# dc26-dev-board-apa102c-3.net
KiCad netlist of a schematic drawn in EAGLE
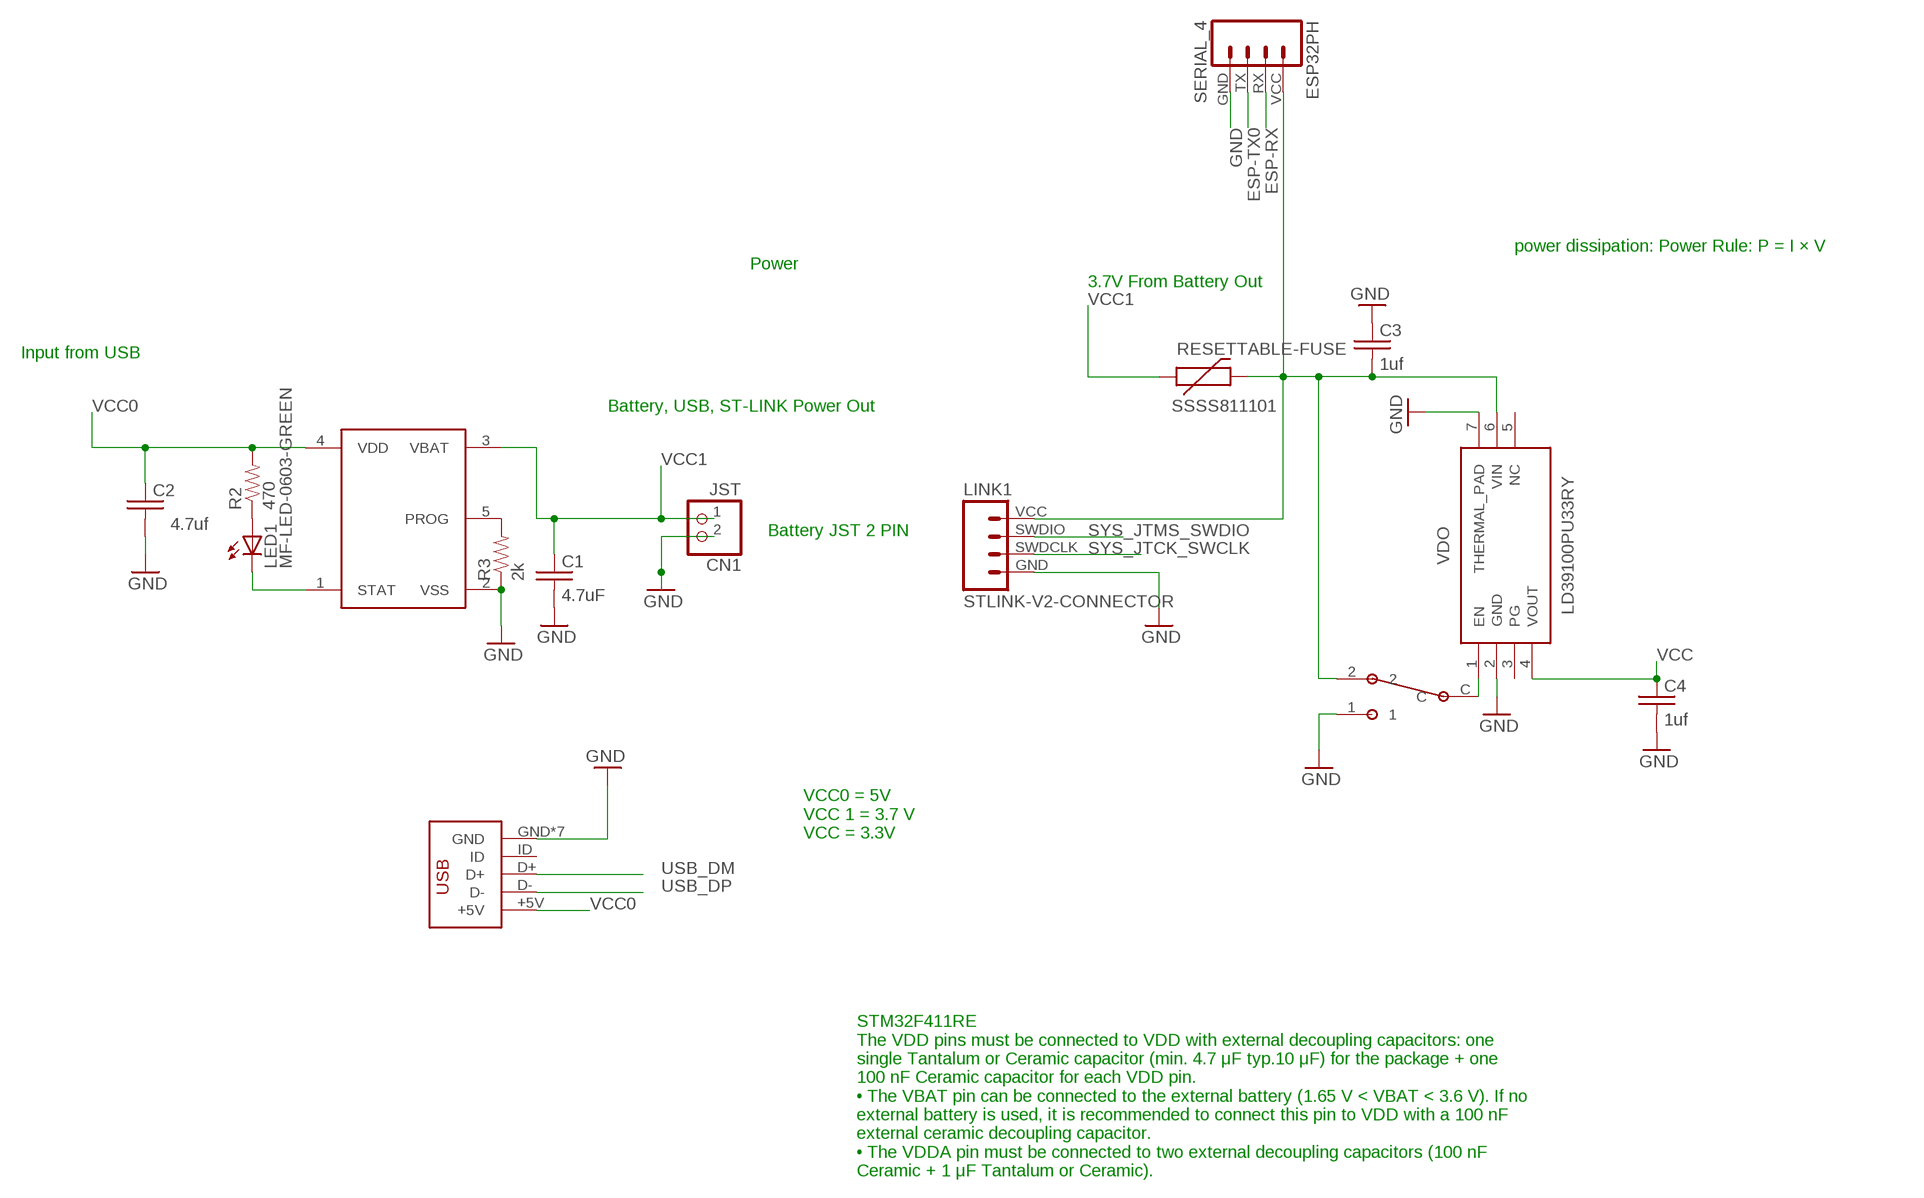
[diagram p0: schematic, sheet 1]
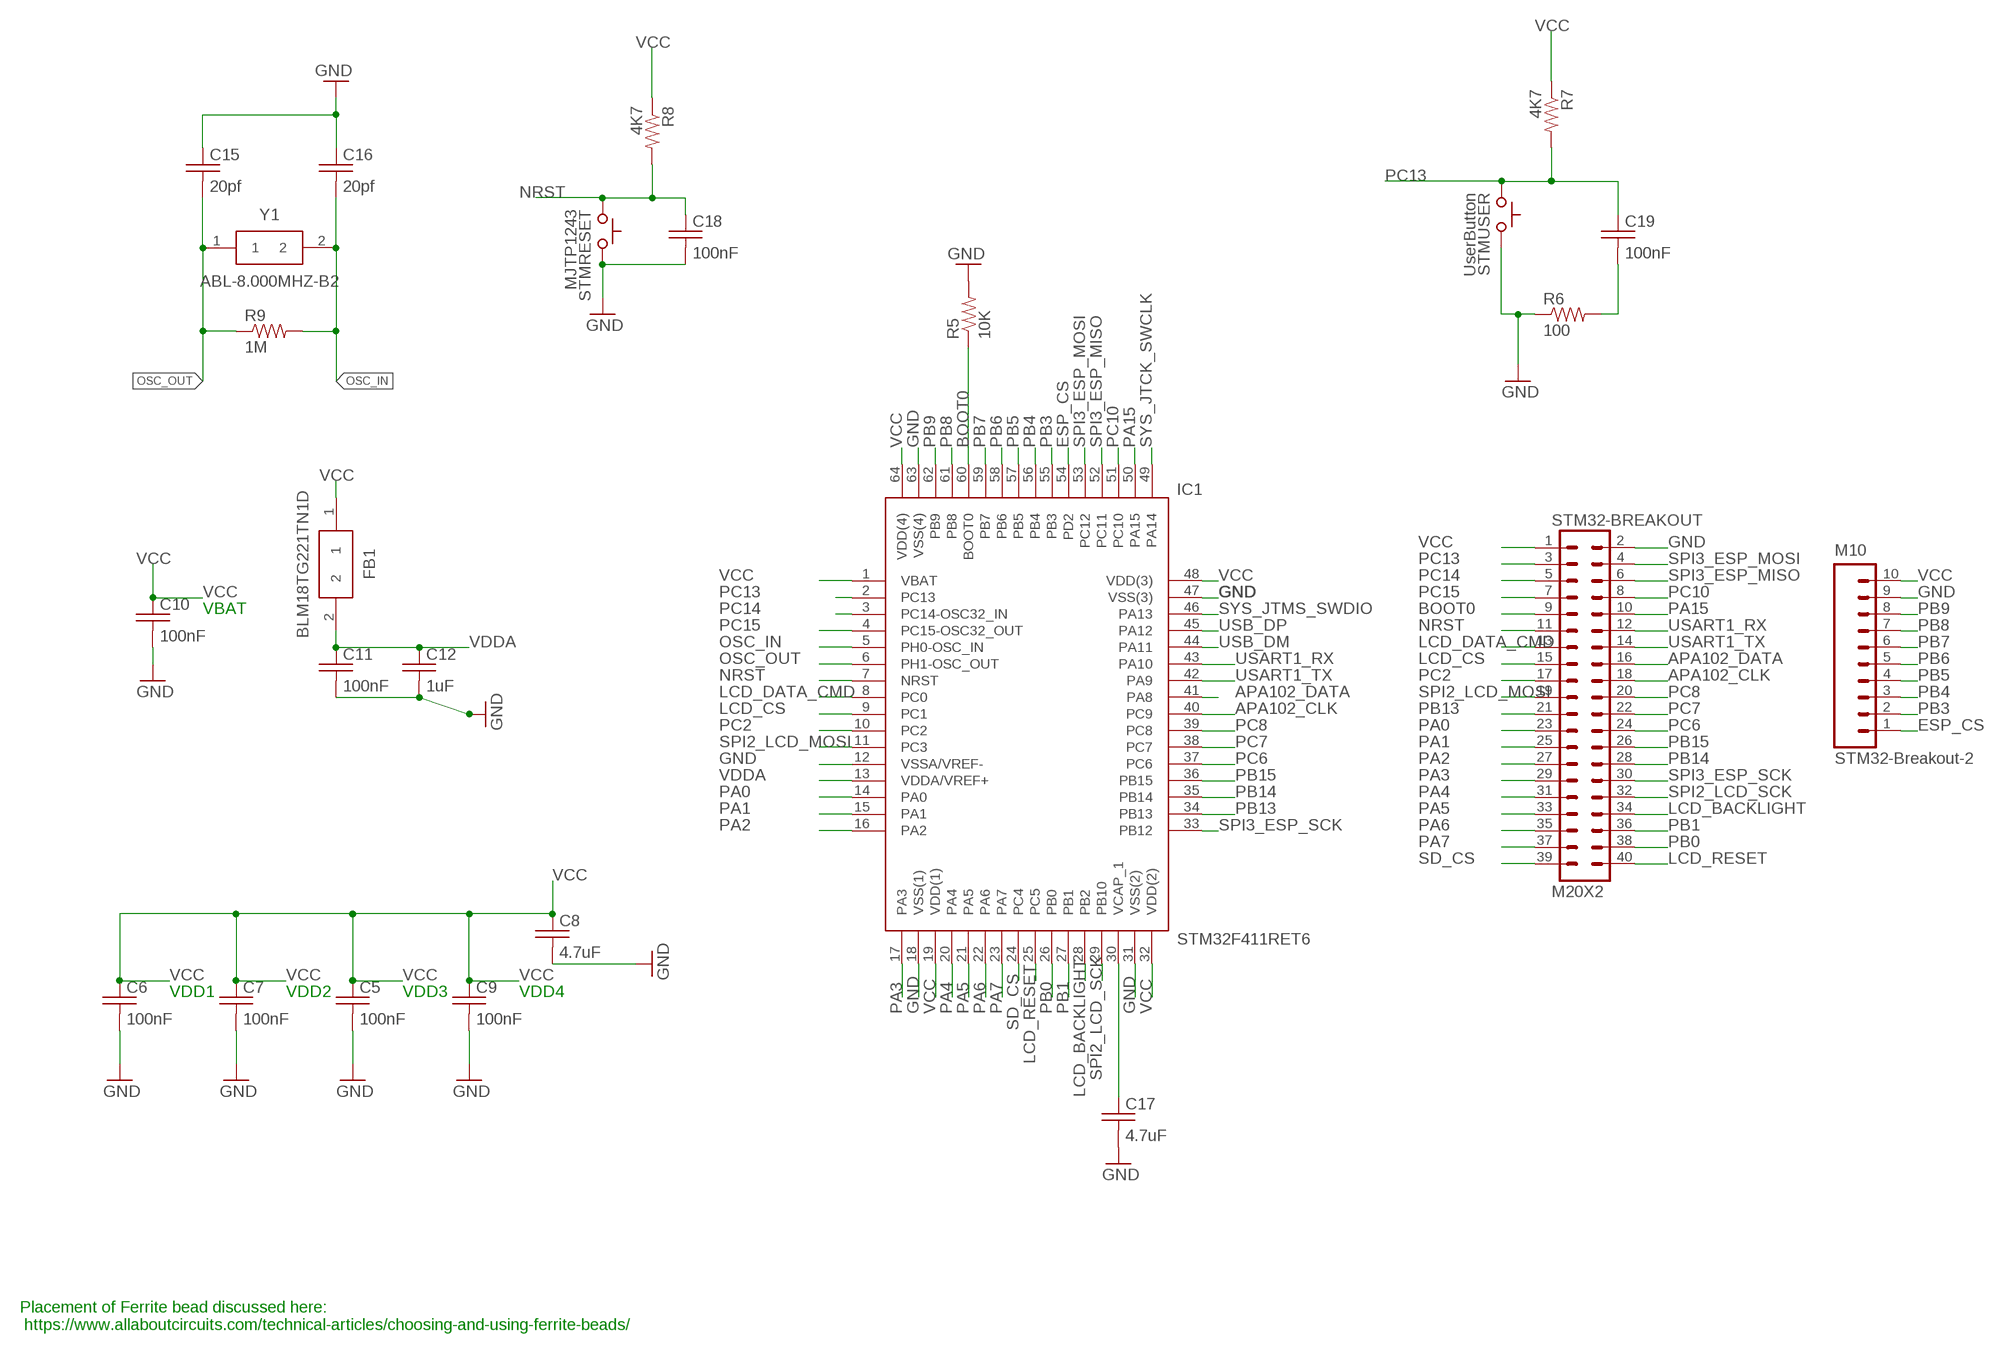
[diagram p1: schematic, sheet 2]
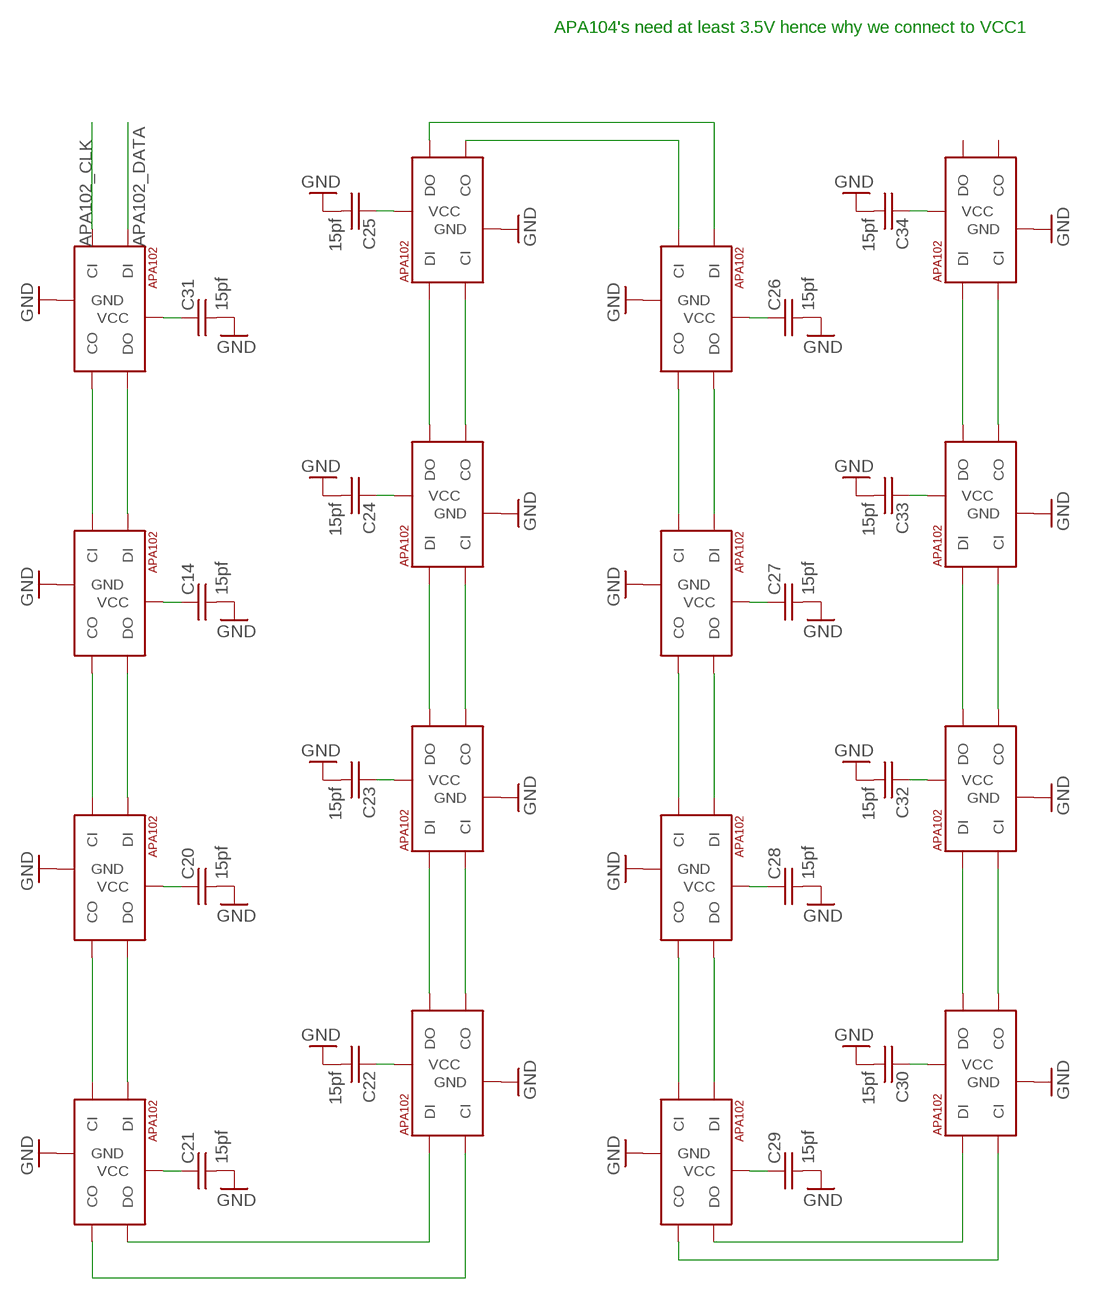
[diagram p2: schematic, sheet 3]
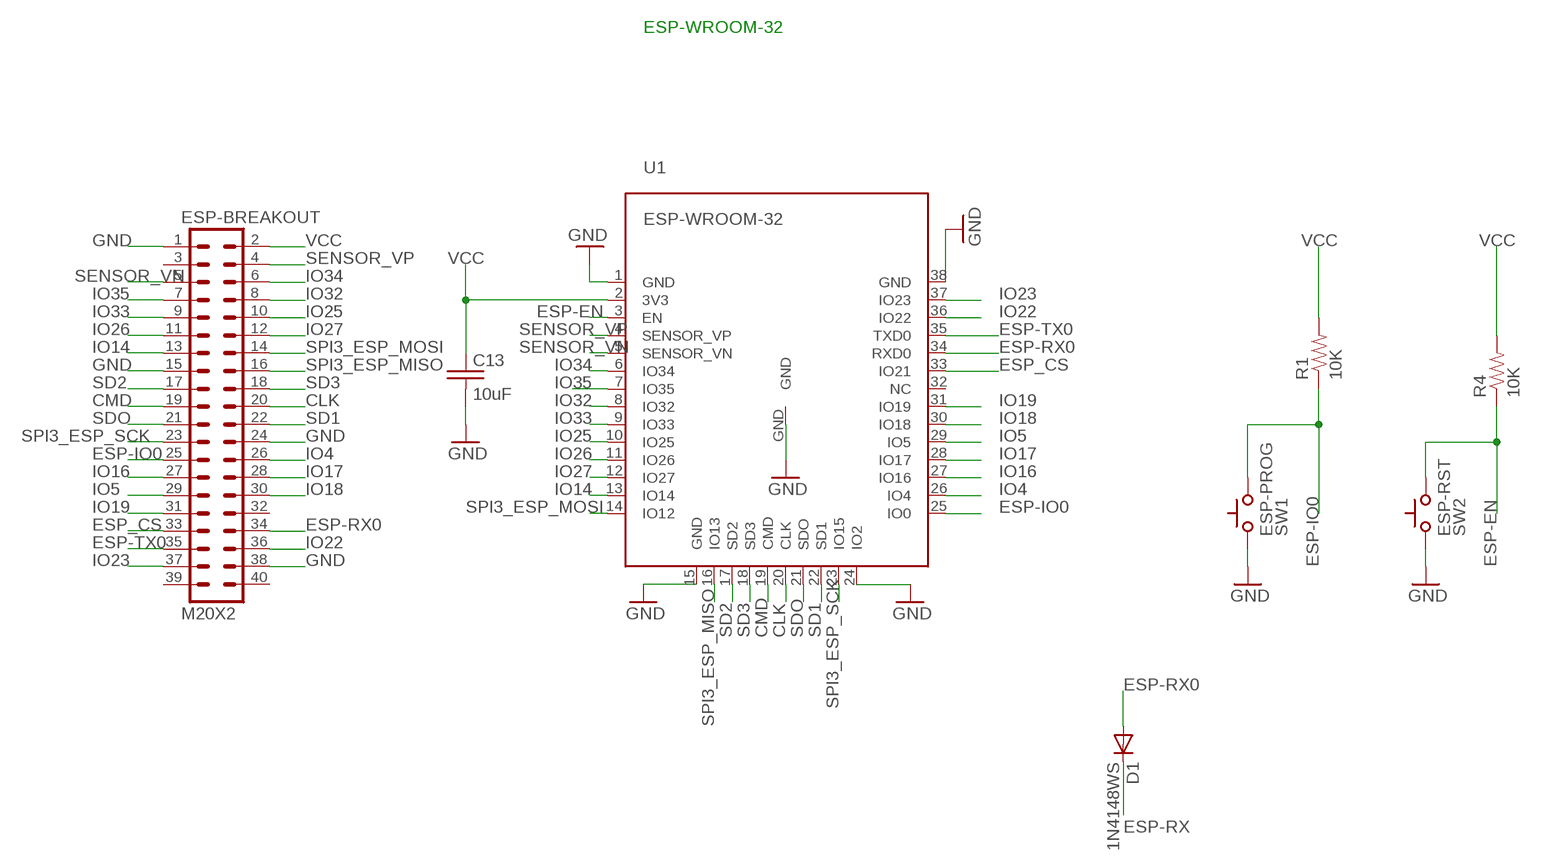
[diagram p3: schematic, sheet 4]
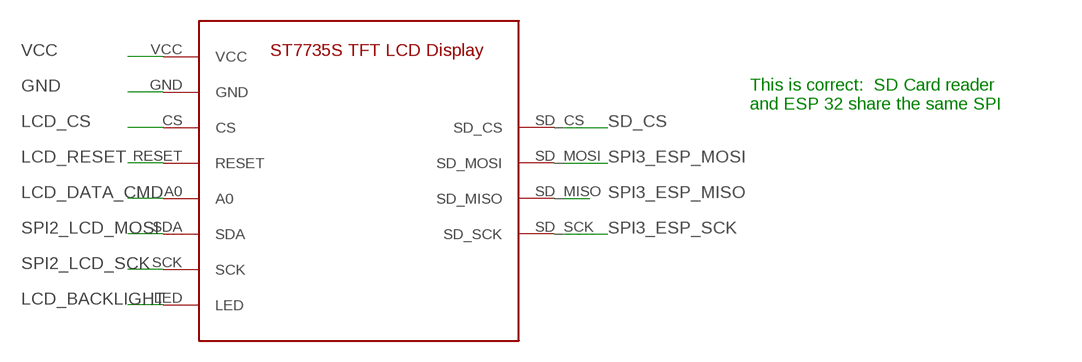
[diagram p4: schematic, sheet 5]
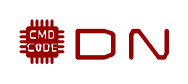
[diagram p5: schematic, sheet 6]
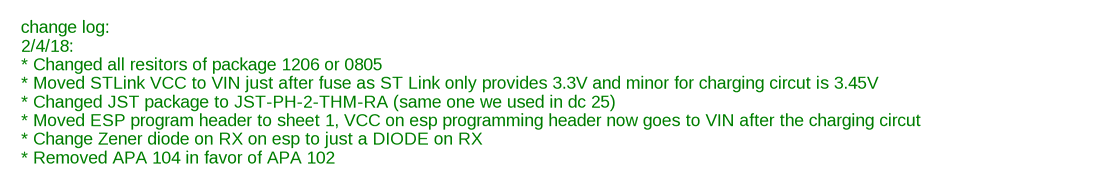
[diagram p6: schematic, sheet 7]

(export (version "E")
  (design (tool "Eeschema 10.0.6"))
  (components
    (comp (ref "C5")
      (value "100nF")
      (footprint "eagle-import:C0805")
      (libsource (lib "eagle-import") (part "C-USC0805"))
    )
    (comp (ref "C6")
      (value "100nF")
      (footprint "eagle-import:C0805")
      (libsource (lib "eagle-import") (part "C-USC0805"))
    )
    (comp (ref "C7")
      (value "100nF")
      (footprint "eagle-import:C0805")
      (libsource (lib "eagle-import") (part "C-USC0805"))
    )
    (comp (ref "C8")
      (value "4.7uF")
      (footprint "eagle-import:C0805")
      (libsource (lib "eagle-import") (part "C-USC0805"))
    )
    (comp (ref "C9")
      (value "100nF")
      (footprint "eagle-import:C0805")
      (libsource (lib "eagle-import") (part "C-USC0805"))
    )
    (comp (ref "C10")
      (value "100nF")
      (footprint "eagle-import:C0805")
      (libsource (lib "eagle-import") (part "C-USC0805"))
    )
    (comp (ref "C11")
      (value "100nF")
      (footprint "eagle-import:C0805")
      (libsource (lib "eagle-import") (part "C-USC0805"))
    )
    (comp (ref "C12")
      (value "1uF")
      (footprint "eagle-import:C0805")
      (libsource (lib "eagle-import") (part "C-USC0805"))
    )
    (comp (ref "C15")
      (value "20pf")
      (footprint "eagle-import:C0805")
      (libsource (lib "eagle-import") (part "C-USC0805"))
    )
    (comp (ref "C16")
      (value "20pf")
      (footprint "eagle-import:C0805")
      (libsource (lib "eagle-import") (part "C-USC0805"))
    )
    (comp (ref "C17")
      (value "4.7uF")
      (footprint "eagle-import:C0805")
      (libsource (lib "eagle-import") (part "C-USC0805"))
    )
    (comp (ref "C18")
      (value "100nF")
      (footprint "eagle-import:C0805")
      (libsource (lib "eagle-import") (part "C-USC0805"))
    )
    (comp (ref "C19")
      (value "100nF")
      (footprint "eagle-import:C0805")
      (libsource (lib "eagle-import") (part "C-USC0805"))
    )
    (comp (ref "FB1")
      (value "BLM18TG221TN1D")
      (footprint "eagle-import:BEADC1608X75N")
      (fields (field (name "RS_PART_NUMBER") "6197526"))
      (libsource (lib "eagle-import") (part "BLM18TG221TN1D"))
    )
    (comp (ref "IC1")
      (value "STM32F411RET6")
      (footprint "eagle-import:QFP50P1200X1200X160-64N")
      (fields (field (name "RS_PART_NUMBER") "1106617P"))
      (libsource (lib "eagle-import") (part "STM32F411RET6"))
    )
    (comp (ref "M10")
      (value "STM32-Breakout-2")
      (footprint "eagle-import:1X10")
      (libsource (lib "eagle-import") (part "M10SILK_FEMALE_PTH"))
    )
    (comp (ref "R5")
      (value "10K")
      (footprint "eagle-import:0805")
      (libsource (lib "eagle-import") (part "RESISTOR0805-RES"))
    )
    (comp (ref "R6")
      (value "100")
      (footprint "eagle-import:0805")
      (libsource (lib "eagle-import") (part "RESISTOR0805-RES"))
    )
    (comp (ref "R7")
      (value "4K7")
      (footprint "eagle-import:0805")
      (libsource (lib "eagle-import") (part "RESISTOR0805-RES"))
    )
    (comp (ref "R8")
      (value "4K7")
      (footprint "eagle-import:0805")
      (libsource (lib "eagle-import") (part "RESISTOR0805-RES"))
    )
    (comp (ref "R9")
      (value "1M")
      (footprint "eagle-import:0805")
      (libsource (lib "eagle-import") (part "RESISTOR0805-RES"))
    )
    (comp (ref "STM32-BREAKOUT")
      (value "M20X2")
      (footprint "eagle-import:2X20")
      (libsource (lib "eagle-import") (part "M20X2"))
    )
    (comp (ref "STMRESET")
      (value "MJTP1243")
      (footprint "eagle-import:TACTILE-2PIN-NARROW")
      (libsource (lib "eagle-import") (part "SWITCH_TACTILETACTILE-2PIN-NARROW"))
    )
    (comp (ref "STMUSER")
      (value "UserButton")
      (footprint "eagle-import:TACTILE-2PIN-NARROW")
      (libsource (lib "eagle-import") (part "SWITCH_TACTILETACTILE-2PIN-NARROW"))
    )
    (comp (ref "Y1")
      (value "ABL-8.000MHZ-B2")
      (footprint "eagle-import:HC_49US_(AT49)PTH")
      (libsource (lib "eagle-import") (part "ABL-8.000MHZ-B2"))
    )
    (comp (ref "C14")
      (value "15pf")
      (footprint "eagle-import:C0805")
      (libsource (lib "eagle-import") (part "C-USC0805"))
    )
    (comp (ref "C20")
      (value "15pf")
      (footprint "eagle-import:C0805")
      (libsource (lib "eagle-import") (part "C-USC0805"))
    )
    (comp (ref "C21")
      (value "15pf")
      (footprint "eagle-import:C0805")
      (libsource (lib "eagle-import") (part "C-USC0805"))
    )
    (comp (ref "C22")
      (value "15pf")
      (footprint "eagle-import:C0805")
      (libsource (lib "eagle-import") (part "C-USC0805"))
    )
    (comp (ref "C23")
      (value "15pf")
      (footprint "eagle-import:C0805")
      (libsource (lib "eagle-import") (part "C-USC0805"))
    )
    (comp (ref "C24")
      (value "15pf")
      (footprint "eagle-import:C0805")
      (libsource (lib "eagle-import") (part "C-USC0805"))
    )
    (comp (ref "C25")
      (value "15pf")
      (footprint "eagle-import:C0805")
      (libsource (lib "eagle-import") (part "C-USC0805"))
    )
    (comp (ref "C26")
      (value "15pf")
      (footprint "eagle-import:C0805")
      (libsource (lib "eagle-import") (part "C-USC0805"))
    )
    (comp (ref "C27")
      (value "15pf")
      (footprint "eagle-import:C0805")
      (libsource (lib "eagle-import") (part "C-USC0805"))
    )
    (comp (ref "C28")
      (value "15pf")
      (footprint "eagle-import:C0805")
      (libsource (lib "eagle-import") (part "C-USC0805"))
    )
    (comp (ref "C29")
      (value "15pf")
      (footprint "eagle-import:C0805")
      (libsource (lib "eagle-import") (part "C-USC0805"))
    )
    (comp (ref "C30")
      (value "15pf")
      (footprint "eagle-import:C0805")
      (libsource (lib "eagle-import") (part "C-USC0805"))
    )
    (comp (ref "C31")
      (value "15pf")
      (footprint "eagle-import:C0805")
      (libsource (lib "eagle-import") (part "C-USC0805"))
    )
    (comp (ref "C32")
      (value "15pf")
      (footprint "eagle-import:C0805")
      (libsource (lib "eagle-import") (part "C-USC0805"))
    )
    (comp (ref "C33")
      (value "15pf")
      (footprint "eagle-import:C0805")
      (libsource (lib "eagle-import") (part "C-USC0805"))
    )
    (comp (ref "C34")
      (value "15pf")
      (footprint "eagle-import:C0805")
      (libsource (lib "eagle-import") (part "C-USC0805"))
    )
    (comp (ref "U$5")
      (value "APA1025050")
      (footprint "eagle-import:APA102_5050")
      (libsource (lib "eagle-import") (part "APA1025050"))
    )
    (comp (ref "U$6")
      (value "APA1025050")
      (footprint "eagle-import:APA102_5050")
      (libsource (lib "eagle-import") (part "APA1025050"))
    )
    (comp (ref "U$7")
      (value "APA1025050")
      (footprint "eagle-import:APA102_5050")
      (libsource (lib "eagle-import") (part "APA1025050"))
    )
    (comp (ref "U$8")
      (value "APA1025050")
      (footprint "eagle-import:APA102_5050")
      (libsource (lib "eagle-import") (part "APA1025050"))
    )
    (comp (ref "U$9")
      (value "APA1025050")
      (footprint "eagle-import:APA102_5050")
      (libsource (lib "eagle-import") (part "APA1025050"))
    )
    (comp (ref "U$10")
      (value "APA1025050")
      (footprint "eagle-import:APA102_5050")
      (libsource (lib "eagle-import") (part "APA1025050"))
    )
    (comp (ref "U$11")
      (value "APA1025050")
      (footprint "eagle-import:APA102_5050")
      (libsource (lib "eagle-import") (part "APA1025050"))
    )
    (comp (ref "U$12")
      (value "APA1025050")
      (footprint "eagle-import:APA102_5050")
      (libsource (lib "eagle-import") (part "APA1025050"))
    )
    (comp (ref "U$13")
      (value "APA1025050")
      (footprint "eagle-import:APA102_5050")
      (libsource (lib "eagle-import") (part "APA1025050"))
    )
    (comp (ref "U$14")
      (value "APA1025050")
      (footprint "eagle-import:APA102_5050")
      (libsource (lib "eagle-import") (part "APA1025050"))
    )
    (comp (ref "U$15")
      (value "APA1025050")
      (footprint "eagle-import:APA102_5050")
      (libsource (lib "eagle-import") (part "APA1025050"))
    )
    (comp (ref "U$16")
      (value "APA1025050")
      (footprint "eagle-import:APA102_5050")
      (libsource (lib "eagle-import") (part "APA1025050"))
    )
    (comp (ref "U$17")
      (value "APA1025050")
      (footprint "eagle-import:APA102_5050")
      (libsource (lib "eagle-import") (part "APA1025050"))
    )
    (comp (ref "U$18")
      (value "APA1025050")
      (footprint "eagle-import:APA102_5050")
      (libsource (lib "eagle-import") (part "APA1025050"))
    )
    (comp (ref "U$19")
      (value "APA1025050")
      (footprint "eagle-import:APA102_5050")
      (libsource (lib "eagle-import") (part "APA1025050"))
    )
    (comp (ref "U$20")
      (value "APA1025050")
      (footprint "eagle-import:APA102_5050")
      (libsource (lib "eagle-import") (part "APA1025050"))
    )
    (comp (ref "U$1")
      (value "ST7735S_LCD_MODULE")
      (footprint "eagle-import:ST7735S_LCD_DISPLAY")
      (libsource (lib "eagle-import") (part "ST7735S_LCD_MODULE"))
    )
    (comp (ref "C13")
      (value "10uF")
      (footprint "eagle-import:C0805")
      (libsource (lib "eagle-import") (part "C-USC0805"))
    )
    (comp (ref "D1")
      (value "1N4148WS")
      (footprint "eagle-import:SOD-323")
      (libsource (lib "eagle-import") (part "DIODESOD"))
    )
    (comp (ref "ESP-BREAKOUT")
      (value "M20X2")
      (footprint "eagle-import:2X20")
      (libsource (lib "eagle-import") (part "M20X2"))
    )
    (comp (ref "ESP-PROG")
      (value "SW1")
      (footprint "eagle-import:TACTILE-2PIN-NARROW")
      (libsource (lib "eagle-import") (part "SWITCH_TACTILETACTILE-2PIN-NARROW"))
    )
    (comp (ref "ESP-RST")
      (value "SW2")
      (footprint "eagle-import:TACTILE-2PIN-NARROW")
      (libsource (lib "eagle-import") (part "SWITCH_TACTILETACTILE-2PIN-NARROW"))
    )
    (comp (ref "R1")
      (value "10K")
      (footprint "eagle-import:0805")
      (libsource (lib "eagle-import") (part "RESISTOR0805-RES"))
    )
    (comp (ref "R4")
      (value "10K")
      (footprint "eagle-import:0805")
      (libsource (lib "eagle-import") (part "RESISTOR0805-RES"))
    )
    (comp (ref "U1")
      (value "ESP-WROOM-32")
      (footprint "eagle-import:ESP-WROOM-32")
      (libsource (lib "eagle-import") (part "ESP-WROOM-32"))
    )
    (comp (ref "U$2")
      (value "CMD_C0DE_LOGO")
      (footprint "eagle-import:CMD_C0DE_LOGO")
      (libsource (lib "eagle-import") (part "CMD_C0DE_LOGO"))
    )
    (comp (ref "U$3")
      (value "DARKNET_DD")
      (footprint "eagle-import:DARKNET_D")
      (libsource (lib "eagle-import") (part "DARKNET_DD"))
    )
    (comp (ref "U$4")
      (value "DARKNET_NN")
      (footprint "eagle-import:DARKNET_N")
      (libsource (lib "eagle-import") (part "DARKNET_NN"))
    )
    (comp (ref "C1")
      (value "4.7uF")
      (footprint "eagle-import:C0805")
      (libsource (lib "eagle-import") (part "C-USC0805"))
    )
    (comp (ref "C2")
      (value "4.7uf")
      (footprint "eagle-import:C0805")
      (libsource (lib "eagle-import") (part "C-USC0805"))
    )
    (comp (ref "C3")
      (value "1uf")
      (footprint "eagle-import:C0805")
      (libsource (lib "eagle-import") (part "C-USC0805"))
    )
    (comp (ref "C4")
      (value "1uf")
      (footprint "eagle-import:C0805")
      (libsource (lib "eagle-import") (part "C-USC0805"))
    )
    (comp (ref "CHARGING_CIRCUT")
      (value "MCP73831")
      (footprint "eagle-import:SOT23-5")
      (libsource (lib "eagle-import") (part "DS21984E"))
    )
    (comp (ref "CN1")
      (value "JST")
      (footprint "eagle-import:JST-PH-2-THM-RA")
      (libsource (lib "eagle-import") (part "JST_2PIN-THM-RA"))
    )
    (comp (ref "ESP32PH")
      (value "SERIAL_4")
      (footprint "eagle-import:SERIAL_HEADER_4")
      (libsource (lib "eagle-import") (part "SERIAL_4"))
    )
    (comp (ref "LED1")
      (value "MF-LED-0603-GREEN")
      (footprint "eagle-import:LED-1206")
      (libsource (lib "eagle-import") (part "LED1206"))
    )
    (comp (ref "LINK1")
      (value "STLINK-V2-CONNECTOR")
      (footprint "eagle-import:1X04")
      (libsource (lib "eagle-import") (part "STLINK-V2-CONNECTOR"))
    )
    (comp (ref "P1")
      (value "SSSS811101")
      (footprint "eagle-import:SPDT_SSAJ120100")
      (libsource (lib "eagle-import") (part "SWITCH_SPDT"))
    )
    (comp (ref "R2")
      (value "470")
      (footprint "eagle-import:0805")
      (libsource (lib "eagle-import") (part "RESISTOR0805-RES"))
    )
    (comp (ref "R3")
      (value "2k")
      (footprint "eagle-import:0805")
      (libsource (lib "eagle-import") (part "RESISTOR0805-RES"))
    )
    (comp (ref "RESETTABLE-FUSE")
      (value "SSSS811101")
      (footprint "eagle-import:PTC-1206")
      (libsource (lib "eagle-import") (part "PTCSMD"))
    )
    (comp (ref "USB")
      (value "DX4R005JJ2DX4R005JJ2")
      (footprint "eagle-import:DX4R005JJ2")
      (libsource (lib "eagle-import") (part "DX4R005JJ2DX4R005JJ2"))
    )
    (comp (ref "VDO")
      (value "LD39100PU33RY")
      (footprint "eagle-import:SON95P300X300X90-7N")
      (libsource (lib "eagle-import") (part "LD39100PU33RY"))
    )
  )
  (nets
    (net (code "1") (name "APA102_CLK") (class "Default")
      (node (ref "IC1") (pin "40") (pinfunction "PC9_40") (pintype "passive"))
      (node (ref "STM32-BREAKOUT") (pin "18") (pinfunction "18_18") (pintype "passive"))
      (node (ref "U$8") (pin "5") (pinfunction "CI_5") (pintype "bidirectional"))
    )
    (net (code "2") (name "APA102_DATA") (class "Default")
      (node (ref "IC1") (pin "41") (pinfunction "PA8_41") (pintype "passive"))
      (node (ref "STM32-BREAKOUT") (pin "16") (pinfunction "16_16") (pintype "passive"))
      (node (ref "U$8") (pin "4") (pinfunction "DI_4") (pintype "bidirectional"))
    )
    (net (code "3") (name "BOOT0") (class "Default")
      (node (ref "IC1") (pin "60") (pinfunction "BOOT0_60") (pintype "passive"))
      (node (ref "R5") (pin "1") (pinfunction "1_1") (pintype "passive"))
      (node (ref "STM32-BREAKOUT") (pin "9") (pinfunction "9_9") (pintype "passive"))
    )
    (net (code "4") (name "CLK") (class "Default")
      (node (ref "ESP-BREAKOUT") (pin "20") (pinfunction "20_20") (pintype "passive"))
      (node (ref "U1") (pin "20") (pinfunction "CLK_20") (pintype "bidirectional"))
    )
    (net (code "5") (name "CMD") (class "Default")
      (node (ref "ESP-BREAKOUT") (pin "19") (pinfunction "19_19") (pintype "passive"))
      (node (ref "U1") (pin "19") (pinfunction "CMD_19") (pintype "bidirectional"))
    )
    (net (code "6") (name "ESP-EN") (class "Default")
      (node (ref "ESP-RST") (pin "P$1") (pinfunction "A_P$1") (pintype "passive"))
      (node (ref "R4") (pin "1") (pinfunction "1_1") (pintype "passive"))
      (node (ref "U1") (pin "3") (pinfunction "EN_3") (pintype "bidirectional"))
    )
    (net (code "7") (name "ESP-IO0") (class "Default")
      (node (ref "ESP-BREAKOUT") (pin "25") (pinfunction "25_25") (pintype "passive"))
      (node (ref "ESP-PROG") (pin "P$1") (pinfunction "A_P$1") (pintype "passive"))
      (node (ref "R1") (pin "1") (pinfunction "1_1") (pintype "passive"))
      (node (ref "U1") (pin "25") (pinfunction "IO0_25") (pintype "bidirectional"))
    )
    (net (code "8") (name "ESP-RX") (class "Default")
      (node (ref "D1") (pin "1") (pinfunction "C_1") (pintype "passive"))
      (node (ref "ESP32PH") (pin "RX") (pinfunction "RX_RX") (pintype "bidirectional"))
    )
    (net (code "9") (name "ESP-RX0") (class "Default")
      (node (ref "D1") (pin "2") (pinfunction "A_2") (pintype "passive"))
      (node (ref "ESP-BREAKOUT") (pin "34") (pinfunction "34_34") (pintype "passive"))
      (node (ref "U1") (pin "34") (pinfunction "RXD0_34") (pintype "bidirectional"))
    )
    (net (code "10") (name "ESP-TX0") (class "Default")
      (node (ref "ESP-BREAKOUT") (pin "35") (pinfunction "35_35") (pintype "passive"))
      (node (ref "ESP32PH") (pin "TX") (pinfunction "TX_TX") (pintype "input"))
      (node (ref "U1") (pin "35") (pinfunction "TXD0_35") (pintype "bidirectional"))
    )
    (net (code "11") (name "ESP_CS") (class "Default")
      (node (ref "ESP-BREAKOUT") (pin "33") (pinfunction "33_33") (pintype "passive"))
      (node (ref "IC1") (pin "54") (pinfunction "PD2_54") (pintype "passive"))
      (node (ref "M10") (pin "1") (pinfunction "1_1") (pintype "passive"))
      (node (ref "U1") (pin "33") (pinfunction "IO21_33") (pintype "bidirectional"))
    )
    (net (code "12") (name "GND") (class "Default")
      (node (ref "C1") (pin "2") (pinfunction "2_2") (pintype "passive"))
      (node (ref "C10") (pin "2") (pinfunction "2_2") (pintype "passive"))
      (node (ref "C11") (pin "2") (pinfunction "2_2") (pintype "passive"))
      (node (ref "C12") (pin "2") (pinfunction "2_2") (pintype "passive"))
      (node (ref "C13") (pin "2") (pinfunction "2_2") (pintype "passive"))
      (node (ref "C14") (pin "2") (pinfunction "2_2") (pintype "passive"))
      (node (ref "C15") (pin "1") (pinfunction "1_1") (pintype "passive"))
      (node (ref "C16") (pin "1") (pinfunction "1_1") (pintype "passive"))
      (node (ref "C17") (pin "2") (pinfunction "2_2") (pintype "passive"))
      (node (ref "C18") (pin "2") (pinfunction "2_2") (pintype "passive"))
      (node (ref "C2") (pin "2") (pinfunction "2_2") (pintype "passive"))
      (node (ref "C20") (pin "2") (pinfunction "2_2") (pintype "passive"))
      (node (ref "C21") (pin "2") (pinfunction "2_2") (pintype "passive"))
      (node (ref "C22") (pin "2") (pinfunction "2_2") (pintype "passive"))
      (node (ref "C23") (pin "2") (pinfunction "2_2") (pintype "passive"))
      (node (ref "C24") (pin "2") (pinfunction "2_2") (pintype "passive"))
      (node (ref "C25") (pin "2") (pinfunction "2_2") (pintype "passive"))
      (node (ref "C26") (pin "2") (pinfunction "2_2") (pintype "passive"))
      (node (ref "C27") (pin "2") (pinfunction "2_2") (pintype "passive"))
      (node (ref "C28") (pin "2") (pinfunction "2_2") (pintype "passive"))
      (node (ref "C29") (pin "2") (pinfunction "2_2") (pintype "passive"))
      (node (ref "C3") (pin "1") (pinfunction "1_1") (pintype "passive"))
      (node (ref "C30") (pin "2") (pinfunction "2_2") (pintype "passive"))
      (node (ref "C31") (pin "2") (pinfunction "2_2") (pintype "passive"))
      (node (ref "C32") (pin "2") (pinfunction "2_2") (pintype "passive"))
      (node (ref "C33") (pin "2") (pinfunction "2_2") (pintype "passive"))
      (node (ref "C34") (pin "2") (pinfunction "2_2") (pintype "passive"))
      (node (ref "C4") (pin "2") (pinfunction "2_2") (pintype "passive"))
      (node (ref "C5") (pin "2") (pinfunction "2_2") (pintype "passive"))
      (node (ref "C6") (pin "2") (pinfunction "2_2") (pintype "passive"))
      (node (ref "C7") (pin "2") (pinfunction "2_2") (pintype "passive"))
      (node (ref "C8") (pin "2") (pinfunction "2_2") (pintype "passive"))
      (node (ref "C9") (pin "2") (pinfunction "2_2") (pintype "passive"))
      (node (ref "CHARGING_CIRCUT") (pin "2") (pinfunction "VSS_2") (pintype "bidirectional"))
      (node (ref "CN1") (pin "2") (pinfunction "1_2") (pintype "passive"))
      (node (ref "ESP-BREAKOUT") (pin "1") (pinfunction "1_1") (pintype "passive"))
      (node (ref "ESP-BREAKOUT") (pin "15") (pinfunction "15_15") (pintype "passive"))
      (node (ref "ESP-BREAKOUT") (pin "24") (pinfunction "24_24") (pintype "passive"))
      (node (ref "ESP-BREAKOUT") (pin "38") (pinfunction "38_38") (pintype "passive"))
      (node (ref "ESP-PROG") (pin "P$2") (pinfunction "C_P$2") (pintype "passive"))
      (node (ref "ESP-RST") (pin "P$2") (pinfunction "C_P$2") (pintype "passive"))
      (node (ref "ESP32PH") (pin "GND") (pinfunction "GND_GND") (pintype "power_in"))
      (node (ref "IC1") (pin "12") (pinfunction "VSSA/VREF-_12") (pintype "passive"))
      (node (ref "IC1") (pin "18") (pinfunction "VSS(1)_18") (pintype "passive"))
      (node (ref "IC1") (pin "31") (pinfunction "VSS(2)_31") (pintype "passive"))
      (node (ref "IC1") (pin "47") (pinfunction "VSS(3)_47") (pintype "passive"))
      (node (ref "IC1") (pin "63") (pinfunction "VSS(4)_63") (pintype "passive"))
      (node (ref "LINK1") (pin "GND") (pinfunction "GND_GND") (pintype "power_in"))
      (node (ref "M10") (pin "9") (pinfunction "9_9") (pintype "passive"))
      (node (ref "P1") (pin "1") (pinfunction "1_1") (pintype "bidirectional"))
      (node (ref "R3") (pin "1") (pinfunction "1_1") (pintype "passive"))
      (node (ref "R5") (pin "2") (pinfunction "2_2") (pintype "passive"))
      (node (ref "R6") (pin "1") (pinfunction "1_1") (pintype "passive"))
      (node (ref "STM32-BREAKOUT") (pin "2") (pinfunction "2_2") (pintype "passive"))
      (node (ref "STMRESET") (pin "P$1") (pinfunction "A_P$1") (pintype "passive"))
      (node (ref "STMUSER") (pin "P$1") (pinfunction "A_P$1") (pintype "passive"))
      (node (ref "U$1") (pin "GND") (pinfunction "GND_GND") (pintype "bidirectional"))
      (node (ref "U$10") (pin "6") (pinfunction "GND_6") (pintype "bidirectional"))
      (node (ref "U$11") (pin "6") (pinfunction "GND_6") (pintype "bidirectional"))
      (node (ref "U$12") (pin "6") (pinfunction "GND_6") (pintype "bidirectional"))
      (node (ref "U$13") (pin "6") (pinfunction "GND_6") (pintype "bidirectional"))
      (node (ref "U$14") (pin "6") (pinfunction "GND_6") (pintype "bidirectional"))
      (node (ref "U$15") (pin "6") (pinfunction "GND_6") (pintype "bidirectional"))
      (node (ref "U$16") (pin "6") (pinfunction "GND_6") (pintype "bidirectional"))
      (node (ref "U$17") (pin "6") (pinfunction "GND_6") (pintype "bidirectional"))
      (node (ref "U$18") (pin "6") (pinfunction "GND_6") (pintype "bidirectional"))
      (node (ref "U$19") (pin "6") (pinfunction "GND_6") (pintype "bidirectional"))
      (node (ref "U$20") (pin "6") (pinfunction "GND_6") (pintype "bidirectional"))
      (node (ref "U$5") (pin "6") (pinfunction "GND_6") (pintype "bidirectional"))
      (node (ref "U$6") (pin "6") (pinfunction "GND_6") (pintype "bidirectional"))
      (node (ref "U$7") (pin "6") (pinfunction "GND_6") (pintype "bidirectional"))
      (node (ref "U$8") (pin "6") (pinfunction "GND_6") (pintype "bidirectional"))
      (node (ref "U$9") (pin "6") (pinfunction "GND_6") (pintype "bidirectional"))
      (node (ref "U1") (pin "1") (pinfunction "GND_1") (pintype "bidirectional"))
      (node (ref "U1") (pin "15") (pinfunction "GND_15") (pintype "bidirectional"))
      (node (ref "U1") (pin "24") (pinfunction "IO2_24") (pintype "bidirectional"))
      (node (ref "U1") (pin "38") (pinfunction "GND_38") (pintype "bidirectional"))
      (node (ref "U1") (pin "GND") (pinfunction "GND_GND") (pintype "bidirectional"))
      (node (ref "USB") (pin "GND") (pinfunction "GND_GND") (pintype "bidirectional"))
      (node (ref "USB") (pin "P$10") (pinfunction "GND_P$10") (pintype "bidirectional"))
      (node (ref "USB") (pin "P$11") (pinfunction "GND_P$11") (pintype "bidirectional"))
      (node (ref "USB") (pin "P$6") (pinfunction "GND_P$6") (pintype "bidirectional"))
      (node (ref "USB") (pin "P$7") (pinfunction "GND_P$7") (pintype "bidirectional"))
      (node (ref "USB") (pin "P$8") (pinfunction "GND_P$8") (pintype "bidirectional"))
      (node (ref "USB") (pin "P$9") (pinfunction "GND_P$9") (pintype "bidirectional"))
      (node (ref "VDO") (pin "2") (pinfunction "GND_2") (pintype "passive"))
      (node (ref "VDO") (pin "7") (pinfunction "THERMAL_PAD_7") (pintype "passive"))
    )
    (net (code "13") (name "IO4") (class "Default")
      (node (ref "ESP-BREAKOUT") (pin "26") (pinfunction "26_26") (pintype "passive"))
      (node (ref "U1") (pin "26") (pinfunction "IO4_26") (pintype "bidirectional"))
    )
    (net (code "14") (name "IO5") (class "Default")
      (node (ref "ESP-BREAKOUT") (pin "29") (pinfunction "29_29") (pintype "passive"))
      (node (ref "U1") (pin "29") (pinfunction "IO5_29") (pintype "bidirectional"))
    )
    (net (code "15") (name "IO14") (class "Default")
      (node (ref "ESP-BREAKOUT") (pin "13") (pinfunction "13_13") (pintype "passive"))
      (node (ref "U1") (pin "13") (pinfunction "IO14_13") (pintype "bidirectional"))
    )
    (net (code "16") (name "IO16") (class "Default")
      (node (ref "ESP-BREAKOUT") (pin "27") (pinfunction "27_27") (pintype "passive"))
      (node (ref "U1") (pin "27") (pinfunction "IO16_27") (pintype "bidirectional"))
    )
    (net (code "17") (name "IO17") (class "Default")
      (node (ref "ESP-BREAKOUT") (pin "28") (pinfunction "28_28") (pintype "passive"))
      (node (ref "U1") (pin "28") (pinfunction "IO17_28") (pintype "bidirectional"))
    )
    (net (code "18") (name "IO18") (class "Default")
      (node (ref "ESP-BREAKOUT") (pin "30") (pinfunction "30_30") (pintype "passive"))
      (node (ref "U1") (pin "30") (pinfunction "IO18_30") (pintype "bidirectional"))
    )
    (net (code "19") (name "IO19") (class "Default")
      (node (ref "ESP-BREAKOUT") (pin "31") (pinfunction "31_31") (pintype "passive"))
      (node (ref "U1") (pin "31") (pinfunction "IO19_31") (pintype "bidirectional"))
    )
    (net (code "20") (name "IO22") (class "Default")
      (node (ref "ESP-BREAKOUT") (pin "36") (pinfunction "36_36") (pintype "passive"))
      (node (ref "U1") (pin "36") (pinfunction "IO22_36") (pintype "bidirectional"))
    )
    (net (code "21") (name "IO23") (class "Default")
      (node (ref "ESP-BREAKOUT") (pin "37") (pinfunction "37_37") (pintype "passive"))
      (node (ref "U1") (pin "37") (pinfunction "IO23_37") (pintype "bidirectional"))
    )
    (net (code "22") (name "IO25") (class "Default")
      (node (ref "ESP-BREAKOUT") (pin "10") (pinfunction "10_10") (pintype "passive"))
      (node (ref "U1") (pin "10") (pinfunction "IO25_10") (pintype "bidirectional"))
    )
    (net (code "23") (name "IO26") (class "Default")
      (node (ref "ESP-BREAKOUT") (pin "11") (pinfunction "11_11") (pintype "passive"))
      (node (ref "U1") (pin "11") (pinfunction "IO26_11") (pintype "bidirectional"))
    )
    (net (code "24") (name "IO27") (class "Default")
      (node (ref "ESP-BREAKOUT") (pin "12") (pinfunction "12_12") (pintype "passive"))
      (node (ref "U1") (pin "12") (pinfunction "IO27_12") (pintype "bidirectional"))
    )
    (net (code "25") (name "IO32") (class "Default")
      (node (ref "ESP-BREAKOUT") (pin "8") (pinfunction "8_8") (pintype "passive"))
      (node (ref "U1") (pin "8") (pinfunction "IO32_8") (pintype "bidirectional"))
    )
    (net (code "26") (name "IO33") (class "Default")
      (node (ref "ESP-BREAKOUT") (pin "9") (pinfunction "9_9") (pintype "passive"))
      (node (ref "U1") (pin "9") (pinfunction "IO33_9") (pintype "bidirectional"))
    )
    (net (code "27") (name "IO34") (class "Default")
      (node (ref "ESP-BREAKOUT") (pin "6") (pinfunction "6_6") (pintype "passive"))
      (node (ref "U1") (pin "6") (pinfunction "IO34_6") (pintype "bidirectional"))
    )
    (net (code "28") (name "IO35") (class "Default")
      (node (ref "ESP-BREAKOUT") (pin "7") (pinfunction "7_7") (pintype "passive"))
      (node (ref "U1") (pin "7") (pinfunction "IO35_7") (pintype "bidirectional"))
    )
    (net (code "29") (name "LCD_BACKLIGHT") (class "Default")
      (node (ref "IC1") (pin "28") (pinfunction "PB2_28") (pintype "passive"))
      (node (ref "STM32-BREAKOUT") (pin "34") (pinfunction "34_34") (pintype "passive"))
      (node (ref "U$1") (pin "LED") (pinfunction "LED_LED") (pintype "bidirectional"))
    )
    (net (code "30") (name "LCD_CS") (class "Default")
      (node (ref "IC1") (pin "9") (pinfunction "PC1_9") (pintype "passive"))
      (node (ref "STM32-BREAKOUT") (pin "15") (pinfunction "15_15") (pintype "passive"))
      (node (ref "U$1") (pin "CS") (pinfunction "CS_CS") (pintype "bidirectional"))
    )
    (net (code "31") (name "LCD_DATA_CMD") (class "Default")
      (node (ref "IC1") (pin "8") (pinfunction "PC0_8") (pintype "passive"))
      (node (ref "STM32-BREAKOUT") (pin "13") (pinfunction "13_13") (pintype "passive"))
      (node (ref "U$1") (pin "A0") (pinfunction "A0_A0") (pintype "bidirectional"))
    )
    (net (code "32") (name "LCD_RESET") (class "Default")
      (node (ref "IC1") (pin "25") (pinfunction "PC5_25") (pintype "passive"))
      (node (ref "STM32-BREAKOUT") (pin "40") (pinfunction "40_40") (pintype "passive"))
      (node (ref "U$1") (pin "RESET") (pinfunction "RESET_RESET") (pintype "bidirectional"))
    )
    (net (code "33") (name "NRST") (class "Default")
      (node (ref "C18") (pin "1") (pinfunction "1_1") (pintype "passive"))
      (node (ref "IC1") (pin "7") (pinfunction "NRST_7") (pintype "passive"))
      (node (ref "R8") (pin "2") (pinfunction "2_2") (pintype "passive"))
      (node (ref "STM32-BREAKOUT") (pin "11") (pinfunction "11_11") (pintype "passive"))
      (node (ref "STMRESET") (pin "P$2") (pinfunction "C_P$2") (pintype "passive"))
    )
    (net (code "34") (name "Net-(C19-Pad2)") (class "Default")
      (node (ref "C19") (pin "2") (pinfunction "2_2") (pintype "passive"))
      (node (ref "R6") (pin "2") (pinfunction "2_2") (pintype "passive"))
    )
    (net (code "35") (name "Net-(CHARGING_CIRCUT-PROG)") (class "Default")
      (node (ref "CHARGING_CIRCUT") (pin "5") (pinfunction "PROG_5") (pintype "bidirectional"))
      (node (ref "R3") (pin "2") (pinfunction "2_2") (pintype "passive"))
    )
    (net (code "36") (name "Net-(CHARGING_CIRCUT-STAT)") (class "Default")
      (node (ref "CHARGING_CIRCUT") (pin "1") (pinfunction "STAT_1") (pintype "bidirectional"))
      (node (ref "LED1") (pin "C") (pinfunction "C_C") (pintype "output"))
    )
    (net (code "37") (name "Net-(IC1-VCAP_1)") (class "Default")
      (node (ref "C17") (pin "1") (pinfunction "1_1") (pintype "passive"))
      (node (ref "IC1") (pin "30") (pinfunction "VCAP_1_30") (pintype "passive"))
    )
    (net (code "38") (name "Net-(LED1-PadA)") (class "Default")
      (node (ref "LED1") (pin "A") (pinfunction "A_A") (pintype "input"))
      (node (ref "R2") (pin "1") (pinfunction "1_1") (pintype "passive"))
    )
    (net (code "39") (name "Net-(U$5-CI)") (class "Default")
      (node (ref "U$5") (pin "5") (pinfunction "CI_5") (pintype "bidirectional"))
      (node (ref "U$8") (pin "2") (pinfunction "CO_2") (pintype "bidirectional"))
    )
    (net (code "40") (name "Net-(U$5-CO)") (class "Default")
      (node (ref "U$5") (pin "2") (pinfunction "CO_2") (pintype "bidirectional"))
      (node (ref "U$6") (pin "5") (pinfunction "CI_5") (pintype "bidirectional"))
    )
    (net (code "41") (name "Net-(U$5-DI)") (class "Default")
      (node (ref "U$5") (pin "4") (pinfunction "DI_4") (pintype "bidirectional"))
      (node (ref "U$8") (pin "3") (pinfunction "DO_3") (pintype "bidirectional"))
    )
    (net (code "42") (name "Net-(U$5-DO)") (class "Default")
      (node (ref "U$5") (pin "3") (pinfunction "DO_3") (pintype "bidirectional"))
      (node (ref "U$6") (pin "4") (pinfunction "DI_4") (pintype "bidirectional"))
    )
    (net (code "43") (name "Net-(U$6-CO)") (class "Default")
      (node (ref "U$6") (pin "2") (pinfunction "CO_2") (pintype "bidirectional"))
      (node (ref "U$7") (pin "5") (pinfunction "CI_5") (pintype "bidirectional"))
    )
    (net (code "44") (name "Net-(U$6-DO)") (class "Default")
      (node (ref "U$6") (pin "3") (pinfunction "DO_3") (pintype "bidirectional"))
      (node (ref "U$7") (pin "4") (pinfunction "DI_4") (pintype "bidirectional"))
    )
    (net (code "45") (name "Net-(U$7-CO)") (class "Default")
      (node (ref "U$7") (pin "2") (pinfunction "CO_2") (pintype "bidirectional"))
      (node (ref "U$9") (pin "5") (pinfunction "CI_5") (pintype "bidirectional"))
    )
    (net (code "46") (name "Net-(U$7-DO)") (class "Default")
      (node (ref "U$7") (pin "3") (pinfunction "DO_3") (pintype "bidirectional"))
      (node (ref "U$9") (pin "4") (pinfunction "DI_4") (pintype "bidirectional"))
    )
    (net (code "47") (name "Net-(U$10-CI)") (class "Default")
      (node (ref "U$10") (pin "5") (pinfunction "CI_5") (pintype "bidirectional"))
      (node (ref "U$9") (pin "2") (pinfunction "CO_2") (pintype "bidirectional"))
    )
    (net (code "48") (name "Net-(U$10-CO)") (class "Default")
      (node (ref "U$10") (pin "2") (pinfunction "CO_2") (pintype "bidirectional"))
      (node (ref "U$11") (pin "5") (pinfunction "CI_5") (pintype "bidirectional"))
    )
    (net (code "49") (name "Net-(U$10-DI)") (class "Default")
      (node (ref "U$10") (pin "4") (pinfunction "DI_4") (pintype "bidirectional"))
      (node (ref "U$9") (pin "3") (pinfunction "DO_3") (pintype "bidirectional"))
    )
    (net (code "50") (name "Net-(U$10-DO)") (class "Default")
      (node (ref "U$10") (pin "3") (pinfunction "DO_3") (pintype "bidirectional"))
      (node (ref "U$11") (pin "4") (pinfunction "DI_4") (pintype "bidirectional"))
    )
    (net (code "51") (name "Net-(U$11-CO)") (class "Default")
      (node (ref "U$11") (pin "2") (pinfunction "CO_2") (pintype "bidirectional"))
      (node (ref "U$12") (pin "5") (pinfunction "CI_5") (pintype "bidirectional"))
    )
    (net (code "52") (name "Net-(U$11-DO)") (class "Default")
      (node (ref "U$11") (pin "3") (pinfunction "DO_3") (pintype "bidirectional"))
      (node (ref "U$12") (pin "4") (pinfunction "DI_4") (pintype "bidirectional"))
    )
    (net (code "53") (name "Net-(U$12-CO)") (class "Default")
      (node (ref "U$12") (pin "2") (pinfunction "CO_2") (pintype "bidirectional"))
      (node (ref "U$13") (pin "5") (pinfunction "CI_5") (pintype "bidirectional"))
    )
    (net (code "54") (name "Net-(U$12-DO)") (class "Default")
      (node (ref "U$12") (pin "3") (pinfunction "DO_3") (pintype "bidirectional"))
      (node (ref "U$13") (pin "4") (pinfunction "DI_4") (pintype "bidirectional"))
    )
    (net (code "55") (name "Net-(U$13-CO)") (class "Default")
      (node (ref "U$13") (pin "2") (pinfunction "CO_2") (pintype "bidirectional"))
      (node (ref "U$14") (pin "5") (pinfunction "CI_5") (pintype "bidirectional"))
    )
    (net (code "56") (name "Net-(U$13-DO)") (class "Default")
      (node (ref "U$13") (pin "3") (pinfunction "DO_3") (pintype "bidirectional"))
      (node (ref "U$14") (pin "4") (pinfunction "DI_4") (pintype "bidirectional"))
    )
    (net (code "57") (name "Net-(U$14-CO)") (class "Default")
      (node (ref "U$14") (pin "2") (pinfunction "CO_2") (pintype "bidirectional"))
      (node (ref "U$15") (pin "5") (pinfunction "CI_5") (pintype "bidirectional"))
    )
    (net (code "58") (name "Net-(U$14-DO)") (class "Default")
      (node (ref "U$14") (pin "3") (pinfunction "DO_3") (pintype "bidirectional"))
      (node (ref "U$15") (pin "4") (pinfunction "DI_4") (pintype "bidirectional"))
    )
    (net (code "59") (name "Net-(U$15-CO)") (class "Default")
      (node (ref "U$15") (pin "2") (pinfunction "CO_2") (pintype "bidirectional"))
      (node (ref "U$16") (pin "5") (pinfunction "CI_5") (pintype "bidirectional"))
    )
    (net (code "60") (name "Net-(U$15-DO)") (class "Default")
      (node (ref "U$15") (pin "3") (pinfunction "DO_3") (pintype "bidirectional"))
      (node (ref "U$16") (pin "4") (pinfunction "DI_4") (pintype "bidirectional"))
    )
    (net (code "61") (name "Net-(U$16-CO)") (class "Default")
      (node (ref "U$16") (pin "2") (pinfunction "CO_2") (pintype "bidirectional"))
      (node (ref "U$17") (pin "5") (pinfunction "CI_5") (pintype "bidirectional"))
    )
    (net (code "62") (name "Net-(U$16-DO)") (class "Default")
      (node (ref "U$16") (pin "3") (pinfunction "DO_3") (pintype "bidirectional"))
      (node (ref "U$17") (pin "4") (pinfunction "DI_4") (pintype "bidirectional"))
    )
    (net (code "63") (name "Net-(U$17-CO)") (class "Default")
      (node (ref "U$17") (pin "2") (pinfunction "CO_2") (pintype "bidirectional"))
      (node (ref "U$18") (pin "5") (pinfunction "CI_5") (pintype "bidirectional"))
    )
    (net (code "64") (name "Net-(U$17-DO)") (class "Default")
      (node (ref "U$17") (pin "3") (pinfunction "DO_3") (pintype "bidirectional"))
      (node (ref "U$18") (pin "4") (pinfunction "DI_4") (pintype "bidirectional"))
    )
    (net (code "65") (name "Net-(U$18-CO)") (class "Default")
      (node (ref "U$18") (pin "2") (pinfunction "CO_2") (pintype "bidirectional"))
      (node (ref "U$19") (pin "5") (pinfunction "CI_5") (pintype "bidirectional"))
    )
    (net (code "66") (name "Net-(U$18-DO)") (class "Default")
      (node (ref "U$18") (pin "3") (pinfunction "DO_3") (pintype "bidirectional"))
      (node (ref "U$19") (pin "4") (pinfunction "DI_4") (pintype "bidirectional"))
    )
    (net (code "67") (name "Net-(U$19-CO)") (class "Default")
      (node (ref "U$19") (pin "2") (pinfunction "CO_2") (pintype "bidirectional"))
      (node (ref "U$20") (pin "5") (pinfunction "CI_5") (pintype "bidirectional"))
    )
    (net (code "68") (name "Net-(U$19-DO)") (class "Default")
      (node (ref "U$19") (pin "3") (pinfunction "DO_3") (pintype "bidirectional"))
      (node (ref "U$20") (pin "4") (pinfunction "DI_4") (pintype "bidirectional"))
    )
    (net (code "69") (name "Net-(VDO-EN)") (class "Default")
      (node (ref "P1") (pin "C") (pinfunction "C_C") (pintype "bidirectional"))
      (node (ref "VDO") (pin "1") (pinfunction "EN_1") (pintype "passive"))
    )
    (net (code "70") (name "OSC_IN") (class "Default")
      (node (ref "C16") (pin "2") (pinfunction "2_2") (pintype "passive"))
      (node (ref "IC1") (pin "5") (pinfunction "PH0-OSC_IN_5") (pintype "passive"))
      (node (ref "R9") (pin "2") (pinfunction "2_2") (pintype "passive"))
      (node (ref "Y1") (pin "2") (pinfunction "2_2") (pintype "passive"))
    )
    (net (code "71") (name "OSC_OUT") (class "Default")
      (node (ref "C15") (pin "2") (pinfunction "2_2") (pintype "passive"))
      (node (ref "IC1") (pin "6") (pinfunction "PH1-OSC_OUT_6") (pintype "passive"))
      (node (ref "R9") (pin "1") (pinfunction "1_1") (pintype "passive"))
      (node (ref "Y1") (pin "1") (pinfunction "1_1") (pintype "passive"))
    )
    (net (code "72") (name "PA0") (class "Default")
      (node (ref "IC1") (pin "14") (pinfunction "PA0_14") (pintype "passive"))
      (node (ref "STM32-BREAKOUT") (pin "23") (pinfunction "23_23") (pintype "passive"))
    )
    (net (code "73") (name "PA1") (class "Default")
      (node (ref "IC1") (pin "15") (pinfunction "PA1_15") (pintype "passive"))
      (node (ref "STM32-BREAKOUT") (pin "25") (pinfunction "25_25") (pintype "passive"))
    )
    (net (code "74") (name "PA2") (class "Default")
      (node (ref "IC1") (pin "16") (pinfunction "PA2_16") (pintype "passive"))
      (node (ref "STM32-BREAKOUT") (pin "27") (pinfunction "27_27") (pintype "passive"))
    )
    (net (code "75") (name "PA3") (class "Default")
      (node (ref "IC1") (pin "17") (pinfunction "PA3_17") (pintype "passive"))
      (node (ref "STM32-BREAKOUT") (pin "29") (pinfunction "29_29") (pintype "passive"))
    )
    (net (code "76") (name "PA4") (class "Default")
      (node (ref "IC1") (pin "20") (pinfunction "PA4_20") (pintype "passive"))
      (node (ref "STM32-BREAKOUT") (pin "31") (pinfunction "31_31") (pintype "passive"))
    )
    (net (code "77") (name "PA5") (class "Default")
      (node (ref "IC1") (pin "21") (pinfunction "PA5_21") (pintype "passive"))
      (node (ref "STM32-BREAKOUT") (pin "33") (pinfunction "33_33") (pintype "passive"))
    )
    (net (code "78") (name "PA6") (class "Default")
      (node (ref "IC1") (pin "22") (pinfunction "PA6_22") (pintype "passive"))
      (node (ref "STM32-BREAKOUT") (pin "35") (pinfunction "35_35") (pintype "passive"))
    )
    (net (code "79") (name "PA7") (class "Default")
      (node (ref "IC1") (pin "23") (pinfunction "PA7_23") (pintype "passive"))
      (node (ref "STM32-BREAKOUT") (pin "37") (pinfunction "37_37") (pintype "passive"))
    )
    (net (code "80") (name "PA15") (class "Default")
      (node (ref "IC1") (pin "50") (pinfunction "PA15_50") (pintype "passive"))
      (node (ref "STM32-BREAKOUT") (pin "10") (pinfunction "10_10") (pintype "passive"))
    )
    (net (code "81") (name "PB0") (class "Default")
      (node (ref "IC1") (pin "26") (pinfunction "PB0_26") (pintype "passive"))
      (node (ref "STM32-BREAKOUT") (pin "38") (pinfunction "38_38") (pintype "passive"))
    )
    (net (code "82") (name "PB1") (class "Default")
      (node (ref "IC1") (pin "27") (pinfunction "PB1_27") (pintype "passive"))
      (node (ref "STM32-BREAKOUT") (pin "36") (pinfunction "36_36") (pintype "passive"))
    )
    (net (code "83") (name "PB3") (class "Default")
      (node (ref "IC1") (pin "55") (pinfunction "PB3_55") (pintype "passive"))
      (node (ref "M10") (pin "2") (pinfunction "2_2") (pintype "passive"))
    )
    (net (code "84") (name "PB4") (class "Default")
      (node (ref "IC1") (pin "56") (pinfunction "PB4_56") (pintype "passive"))
      (node (ref "M10") (pin "3") (pinfunction "3_3") (pintype "passive"))
    )
    (net (code "85") (name "PB5") (class "Default")
      (node (ref "IC1") (pin "57") (pinfunction "PB5_57") (pintype "passive"))
      (node (ref "M10") (pin "4") (pinfunction "4_4") (pintype "passive"))
    )
    (net (code "86") (name "PB6") (class "Default")
      (node (ref "IC1") (pin "58") (pinfunction "PB6_58") (pintype "passive"))
      (node (ref "M10") (pin "5") (pinfunction "5_5") (pintype "passive"))
    )
    (net (code "87") (name "PB7") (class "Default")
      (node (ref "IC1") (pin "59") (pinfunction "PB7_59") (pintype "passive"))
      (node (ref "M10") (pin "6") (pinfunction "6_6") (pintype "passive"))
    )
    (net (code "88") (name "PB8") (class "Default")
      (node (ref "IC1") (pin "61") (pinfunction "PB8_61") (pintype "passive"))
      (node (ref "M10") (pin "7") (pinfunction "7_7") (pintype "passive"))
    )
    (net (code "89") (name "PB9") (class "Default")
      (node (ref "IC1") (pin "62") (pinfunction "PB9_62") (pintype "passive"))
      (node (ref "M10") (pin "8") (pinfunction "8_8") (pintype "passive"))
    )
    (net (code "90") (name "PB13") (class "Default")
      (node (ref "IC1") (pin "34") (pinfunction "PB13_34") (pintype "passive"))
      (node (ref "STM32-BREAKOUT") (pin "21") (pinfunction "21_21") (pintype "passive"))
    )
    (net (code "91") (name "PB14") (class "Default")
      (node (ref "IC1") (pin "35") (pinfunction "PB14_35") (pintype "passive"))
      (node (ref "STM32-BREAKOUT") (pin "28") (pinfunction "28_28") (pintype "passive"))
    )
    (net (code "92") (name "PB15") (class "Default")
      (node (ref "IC1") (pin "36") (pinfunction "PB15_36") (pintype "passive"))
      (node (ref "STM32-BREAKOUT") (pin "26") (pinfunction "26_26") (pintype "passive"))
    )
    (net (code "93") (name "PC2") (class "Default")
      (node (ref "IC1") (pin "10") (pinfunction "PC2_10") (pintype "passive"))
      (node (ref "STM32-BREAKOUT") (pin "17") (pinfunction "17_17") (pintype "passive"))
    )
    (net (code "94") (name "PC6") (class "Default")
      (node (ref "IC1") (pin "37") (pinfunction "PC6_37") (pintype "passive"))
      (node (ref "STM32-BREAKOUT") (pin "24") (pinfunction "24_24") (pintype "passive"))
    )
    (net (code "95") (name "PC7") (class "Default")
      (node (ref "IC1") (pin "38") (pinfunction "PC7_38") (pintype "passive"))
      (node (ref "STM32-BREAKOUT") (pin "22") (pinfunction "22_22") (pintype "passive"))
    )
    (net (code "96") (name "PC8") (class "Default")
      (node (ref "IC1") (pin "39") (pinfunction "PC8_39") (pintype "passive"))
      (node (ref "STM32-BREAKOUT") (pin "20") (pinfunction "20_20") (pintype "passive"))
    )
    (net (code "97") (name "PC10") (class "Default")
      (node (ref "IC1") (pin "51") (pinfunction "PC10_51") (pintype "passive"))
      (node (ref "STM32-BREAKOUT") (pin "8") (pinfunction "8_8") (pintype "passive"))
    )
    (net (code "98") (name "PC13") (class "Default")
      (node (ref "C19") (pin "1") (pinfunction "1_1") (pintype "passive"))
      (node (ref "IC1") (pin "2") (pinfunction "PC13_2") (pintype "passive"))
      (node (ref "R7") (pin "2") (pinfunction "2_2") (pintype "passive"))
      (node (ref "STM32-BREAKOUT") (pin "3") (pinfunction "3_3") (pintype "passive"))
      (node (ref "STMUSER") (pin "P$2") (pinfunction "C_P$2") (pintype "passive"))
    )
    (net (code "99") (name "PC14") (class "Default")
      (node (ref "IC1") (pin "3") (pinfunction "PC14-OSC32_IN_3") (pintype "passive"))
      (node (ref "STM32-BREAKOUT") (pin "5") (pinfunction "5_5") (pintype "passive"))
    )
    (net (code "100") (name "PC15") (class "Default")
      (node (ref "IC1") (pin "4") (pinfunction "PC15-OSC32_OUT_4") (pintype "passive"))
      (node (ref "STM32-BREAKOUT") (pin "7") (pinfunction "7_7") (pintype "passive"))
    )
    (net (code "101") (name "SD1") (class "Default")
      (node (ref "ESP-BREAKOUT") (pin "22") (pinfunction "22_22") (pintype "passive"))
      (node (ref "U1") (pin "22") (pinfunction "SD1_22") (pintype "bidirectional"))
    )
    (net (code "102") (name "SD2") (class "Default")
      (node (ref "ESP-BREAKOUT") (pin "17") (pinfunction "17_17") (pintype "passive"))
      (node (ref "U1") (pin "17") (pinfunction "SD2_17") (pintype "bidirectional"))
    )
    (net (code "103") (name "SD3") (class "Default")
      (node (ref "ESP-BREAKOUT") (pin "18") (pinfunction "18_18") (pintype "passive"))
      (node (ref "U1") (pin "18") (pinfunction "SD3_18") (pintype "bidirectional"))
    )
    (net (code "104") (name "SDO") (class "Default")
      (node (ref "ESP-BREAKOUT") (pin "21") (pinfunction "21_21") (pintype "passive"))
      (node (ref "U1") (pin "21") (pinfunction "SDO_21") (pintype "bidirectional"))
    )
    (net (code "105") (name "SD_CS") (class "Default")
      (node (ref "IC1") (pin "24") (pinfunction "PC4_24") (pintype "passive"))
      (node (ref "STM32-BREAKOUT") (pin "39") (pinfunction "39_39") (pintype "passive"))
      (node (ref "U$1") (pin "SD_CS") (pinfunction "SD_CS_SD_CS") (pintype "bidirectional"))
    )
    (net (code "106") (name "SENSOR_VN") (class "Default")
      (node (ref "ESP-BREAKOUT") (pin "5") (pinfunction "5_5") (pintype "passive"))
      (node (ref "U1") (pin "5") (pinfunction "SENSOR_VN_5") (pintype "bidirectional"))
    )
    (net (code "107") (name "SENSOR_VP") (class "Default")
      (node (ref "ESP-BREAKOUT") (pin "4") (pinfunction "4_4") (pintype "passive"))
      (node (ref "U1") (pin "4") (pinfunction "SENSOR_VP_4") (pintype "bidirectional"))
    )
    (net (code "108") (name "SPI2_LCD_MOSI") (class "Default")
      (node (ref "IC1") (pin "11") (pinfunction "PC3_11") (pintype "passive"))
      (node (ref "STM32-BREAKOUT") (pin "19") (pinfunction "19_19") (pintype "passive"))
      (node (ref "U$1") (pin "SDA") (pinfunction "SDA_SDA") (pintype "bidirectional"))
    )
    (net (code "109") (name "SPI2_LCD_SCK") (class "Default")
      (node (ref "IC1") (pin "29") (pinfunction "PB10_29") (pintype "passive"))
      (node (ref "STM32-BREAKOUT") (pin "32") (pinfunction "32_32") (pintype "passive"))
      (node (ref "U$1") (pin "SCK") (pinfunction "SCK_SCK") (pintype "bidirectional"))
    )
    (net (code "110") (name "SPI3_ESP_MISO") (class "Default")
      (node (ref "ESP-BREAKOUT") (pin "16") (pinfunction "16_16") (pintype "passive"))
      (node (ref "IC1") (pin "52") (pinfunction "PC11_52") (pintype "passive"))
      (node (ref "STM32-BREAKOUT") (pin "6") (pinfunction "6_6") (pintype "passive"))
      (node (ref "U$1") (pin "SD_MISO") (pinfunction "SD_MISO_SD_MISO") (pintype "bidirectional"))
      (node (ref "U1") (pin "16") (pinfunction "IO13_16") (pintype "bidirectional"))
    )
    (net (code "111") (name "SPI3_ESP_MOSI") (class "Default")
      (node (ref "ESP-BREAKOUT") (pin "14") (pinfunction "14_14") (pintype "passive"))
      (node (ref "IC1") (pin "53") (pinfunction "PC12_53") (pintype "passive"))
      (node (ref "STM32-BREAKOUT") (pin "4") (pinfunction "4_4") (pintype "passive"))
      (node (ref "U$1") (pin "SD_MOSI") (pinfunction "SD_MOSI_SD_MOSI") (pintype "bidirectional"))
      (node (ref "U1") (pin "14") (pinfunction "IO12_14") (pintype "bidirectional"))
    )
    (net (code "112") (name "SPI3_ESP_SCK") (class "Default")
      (node (ref "ESP-BREAKOUT") (pin "23") (pinfunction "23_23") (pintype "passive"))
      (node (ref "IC1") (pin "33") (pinfunction "PB12_33") (pintype "passive"))
      (node (ref "STM32-BREAKOUT") (pin "30") (pinfunction "30_30") (pintype "passive"))
      (node (ref "U$1") (pin "SD_SCK") (pinfunction "SD_SCK_SD_SCK") (pintype "bidirectional"))
      (node (ref "U1") (pin "23") (pinfunction "IO15_23") (pintype "bidirectional"))
    )
    (net (code "113") (name "SYS_JTCK_SWCLK") (class "Default")
      (node (ref "IC1") (pin "49") (pinfunction "PA14_49") (pintype "passive"))
      (node (ref "LINK1") (pin "SWDCLK") (pinfunction "SWDCLK_SWDCLK") (pintype "input"))
    )
    (net (code "114") (name "SYS_JTMS_SWDIO") (class "Default")
      (node (ref "IC1") (pin "46") (pinfunction "PA13_46") (pintype "passive"))
      (node (ref "LINK1") (pin "SWDIO") (pinfunction "SWDIO_SWDIO") (pintype "bidirectional"))
    )
    (net (code "115") (name "USART1_RX") (class "Default")
      (node (ref "IC1") (pin "43") (pinfunction "PA10_43") (pintype "passive"))
      (node (ref "STM32-BREAKOUT") (pin "12") (pinfunction "12_12") (pintype "passive"))
    )
    (net (code "116") (name "USART1_TX") (class "Default")
      (node (ref "IC1") (pin "42") (pinfunction "PA9_42") (pintype "passive"))
      (node (ref "STM32-BREAKOUT") (pin "14") (pinfunction "14_14") (pintype "passive"))
    )
    (net (code "117") (name "USB_DM") (class "Default")
      (node (ref "IC1") (pin "44") (pinfunction "PA11_44") (pintype "passive"))
      (node (ref "USB") (pin "D+") (pinfunction "D+_D+") (pintype "bidirectional"))
    )
    (net (code "118") (name "USB_DP") (class "Default")
      (node (ref "IC1") (pin "45") (pinfunction "PA12_45") (pintype "passive"))
      (node (ref "USB") (pin "D-") (pinfunction "D-_D-") (pintype "bidirectional"))
    )
    (net (code "119") (name "VCC") (class "Default")
      (node (ref "C10") (pin "1") (pinfunction "1_1") (pintype "passive"))
      (node (ref "C13") (pin "1") (pinfunction "1_1") (pintype "passive"))
      (node (ref "C4") (pin "1") (pinfunction "1_1") (pintype "passive"))
      (node (ref "C5") (pin "1") (pinfunction "1_1") (pintype "passive"))
      (node (ref "C6") (pin "1") (pinfunction "1_1") (pintype "passive"))
      (node (ref "C7") (pin "1") (pinfunction "1_1") (pintype "passive"))
      (node (ref "C8") (pin "1") (pinfunction "1_1") (pintype "passive"))
      (node (ref "C9") (pin "1") (pinfunction "1_1") (pintype "passive"))
      (node (ref "ESP-BREAKOUT") (pin "2") (pinfunction "2_2") (pintype "passive"))
      (node (ref "FB1") (pin "1") (pinfunction "1_1") (pintype "passive"))
      (node (ref "IC1") (pin "1") (pinfunction "VBAT_1") (pintype "passive"))
      (node (ref "IC1") (pin "19") (pinfunction "VDD(1)_19") (pintype "passive"))
      (node (ref "IC1") (pin "32") (pinfunction "VDD(2)_32") (pintype "passive"))
      (node (ref "IC1") (pin "48") (pinfunction "VDD(3)_48") (pintype "passive"))
      (node (ref "IC1") (pin "64") (pinfunction "VDD(4)_64") (pintype "passive"))
      (node (ref "M10") (pin "10") (pinfunction "10_10") (pintype "passive"))
      (node (ref "R1") (pin "2") (pinfunction "2_2") (pintype "passive"))
      (node (ref "R4") (pin "2") (pinfunction "2_2") (pintype "passive"))
      (node (ref "R7") (pin "1") (pinfunction "1_1") (pintype "passive"))
      (node (ref "R8") (pin "1") (pinfunction "1_1") (pintype "passive"))
      (node (ref "STM32-BREAKOUT") (pin "1") (pinfunction "1_1") (pintype "passive"))
      (node (ref "U$1") (pin "VCC") (pinfunction "VCC_VCC") (pintype "bidirectional"))
      (node (ref "U1") (pin "2") (pinfunction "3V3_2") (pintype "bidirectional"))
      (node (ref "VDO") (pin "4") (pinfunction "VOUT_4") (pintype "passive"))
    )
    (net (code "120") (name "VCC0") (class "Default")
      (node (ref "C2") (pin "1") (pinfunction "1_1") (pintype "passive"))
      (node (ref "CHARGING_CIRCUT") (pin "4") (pinfunction "VDD_4") (pintype "bidirectional"))
      (node (ref "R2") (pin "2") (pinfunction "2_2") (pintype "passive"))
      (node (ref "USB") (pin "+5V") (pinfunction "+5V_+5V") (pintype "bidirectional"))
    )
    (net (code "121") (name "VCC1") (class "Default")
      (node (ref "C1") (pin "1") (pinfunction "1_1") (pintype "passive"))
      (node (ref "CHARGING_CIRCUT") (pin "3") (pinfunction "VBAT_3") (pintype "bidirectional"))
      (node (ref "CN1") (pin "1") (pinfunction "2_1") (pintype "passive"))
      (node (ref "RESETTABLE-FUSE") (pin "1") (pinfunction "1_1") (pintype "bidirectional"))
    )
    (net (code "122") (name "VDDA") (class "Default")
      (node (ref "C11") (pin "1") (pinfunction "1_1") (pintype "passive"))
      (node (ref "C12") (pin "1") (pinfunction "1_1") (pintype "passive"))
      (node (ref "FB1") (pin "2") (pinfunction "2_2") (pintype "passive"))
      (node (ref "IC1") (pin "13") (pinfunction "VDDA/VREF+_13") (pintype "passive"))
    )
    (net (code "123") (name "VIN") (class "Default")
      (node (ref "C14") (pin "1") (pinfunction "1_1") (pintype "passive"))
      (node (ref "C20") (pin "1") (pinfunction "1_1") (pintype "passive"))
      (node (ref "C21") (pin "1") (pinfunction "1_1") (pintype "passive"))
      (node (ref "C22") (pin "1") (pinfunction "1_1") (pintype "passive"))
      (node (ref "C23") (pin "1") (pinfunction "1_1") (pintype "passive"))
      (node (ref "C24") (pin "1") (pinfunction "1_1") (pintype "passive"))
      (node (ref "C25") (pin "1") (pinfunction "1_1") (pintype "passive"))
      (node (ref "C26") (pin "1") (pinfunction "1_1") (pintype "passive"))
      (node (ref "C27") (pin "1") (pinfunction "1_1") (pintype "passive"))
      (node (ref "C28") (pin "1") (pinfunction "1_1") (pintype "passive"))
      (node (ref "C29") (pin "1") (pinfunction "1_1") (pintype "passive"))
      (node (ref "C3") (pin "2") (pinfunction "2_2") (pintype "passive"))
      (node (ref "C30") (pin "1") (pinfunction "1_1") (pintype "passive"))
      (node (ref "C31") (pin "1") (pinfunction "1_1") (pintype "passive"))
      (node (ref "C32") (pin "1") (pinfunction "1_1") (pintype "passive"))
      (node (ref "C33") (pin "1") (pinfunction "1_1") (pintype "passive"))
      (node (ref "C34") (pin "1") (pinfunction "1_1") (pintype "passive"))
      (node (ref "ESP32PH") (pin "VCC") (pinfunction "VCC_VCC") (pintype "power_in"))
      (node (ref "LINK1") (pin "VCC") (pinfunction "VCC_VCC") (pintype "power_in"))
      (node (ref "P1") (pin "2") (pinfunction "2_2") (pintype "bidirectional"))
      (node (ref "RESETTABLE-FUSE") (pin "2") (pinfunction "2_2") (pintype "bidirectional"))
      (node (ref "U$10") (pin "1") (pinfunction "VCC_1") (pintype "bidirectional"))
      (node (ref "U$11") (pin "1") (pinfunction "VCC_1") (pintype "bidirectional"))
      (node (ref "U$12") (pin "1") (pinfunction "VCC_1") (pintype "bidirectional"))
      (node (ref "U$13") (pin "1") (pinfunction "VCC_1") (pintype "bidirectional"))
      (node (ref "U$14") (pin "1") (pinfunction "VCC_1") (pintype "bidirectional"))
      (node (ref "U$15") (pin "1") (pinfunction "VCC_1") (pintype "bidirectional"))
      (node (ref "U$16") (pin "1") (pinfunction "VCC_1") (pintype "bidirectional"))
      (node (ref "U$17") (pin "1") (pinfunction "VCC_1") (pintype "bidirectional"))
      (node (ref "U$18") (pin "1") (pinfunction "VCC_1") (pintype "bidirectional"))
      (node (ref "U$19") (pin "1") (pinfunction "VCC_1") (pintype "bidirectional"))
      (node (ref "U$20") (pin "1") (pinfunction "VCC_1") (pintype "bidirectional"))
      (node (ref "U$5") (pin "1") (pinfunction "VCC_1") (pintype "bidirectional"))
      (node (ref "U$6") (pin "1") (pinfunction "VCC_1") (pintype "bidirectional"))
      (node (ref "U$7") (pin "1") (pinfunction "VCC_1") (pintype "bidirectional"))
      (node (ref "U$8") (pin "1") (pinfunction "VCC_1") (pintype "bidirectional"))
      (node (ref "U$9") (pin "1") (pinfunction "VCC_1") (pintype "bidirectional"))
      (node (ref "VDO") (pin "6") (pinfunction "VIN_6") (pintype "passive"))
    )
    (net (code "124") (name "unconnected-(ESP-BREAKOUT-Pad3)") (class "Default")
      (node (ref "ESP-BREAKOUT") (pin "3") (pinfunction "3_3") (pintype "passive"))
    )
    (net (code "125") (name "unconnected-(ESP-BREAKOUT-Pad32)") (class "Default")
      (node (ref "ESP-BREAKOUT") (pin "32") (pinfunction "32_32") (pintype "passive"))
    )
    (net (code "126") (name "unconnected-(ESP-BREAKOUT-Pad39)") (class "Default")
      (node (ref "ESP-BREAKOUT") (pin "39") (pinfunction "39_39") (pintype "passive"))
    )
    (net (code "127") (name "unconnected-(ESP-BREAKOUT-Pad40)") (class "Default")
      (node (ref "ESP-BREAKOUT") (pin "40") (pinfunction "40_40") (pintype "passive"))
    )
    (net (code "128") (name "unconnected-(U$20-CO-Pad2)") (class "Default")
      (node (ref "U$20") (pin "2") (pinfunction "CO_2") (pintype "bidirectional"))
    )
    (net (code "129") (name "unconnected-(U$20-DO-Pad3)") (class "Default")
      (node (ref "U$20") (pin "3") (pinfunction "DO_3") (pintype "bidirectional"))
    )
    (net (code "130") (name "unconnected-(U1-NC-Pad32)") (class "Default")
      (node (ref "U1") (pin "32") (pinfunction "NC_32") (pintype "bidirectional"))
    )
    (net (code "131") (name "unconnected-(USB-PadID)") (class "Default")
      (node (ref "USB") (pin "ID") (pinfunction "ID_ID") (pintype "bidirectional"))
    )
    (net (code "132") (name "unconnected-(VDO-NC-Pad5)") (class "Default")
      (node (ref "VDO") (pin "5") (pinfunction "NC_5") (pintype "no_connect"))
    )
    (net (code "133") (name "unconnected-(VDO-PG-Pad3)") (class "Default")
      (node (ref "VDO") (pin "3") (pinfunction "PG_3") (pintype "passive"))
    )
  )
)
